# motorcontrol.net
KiCad netlist of a schematic drawn in EAGLE
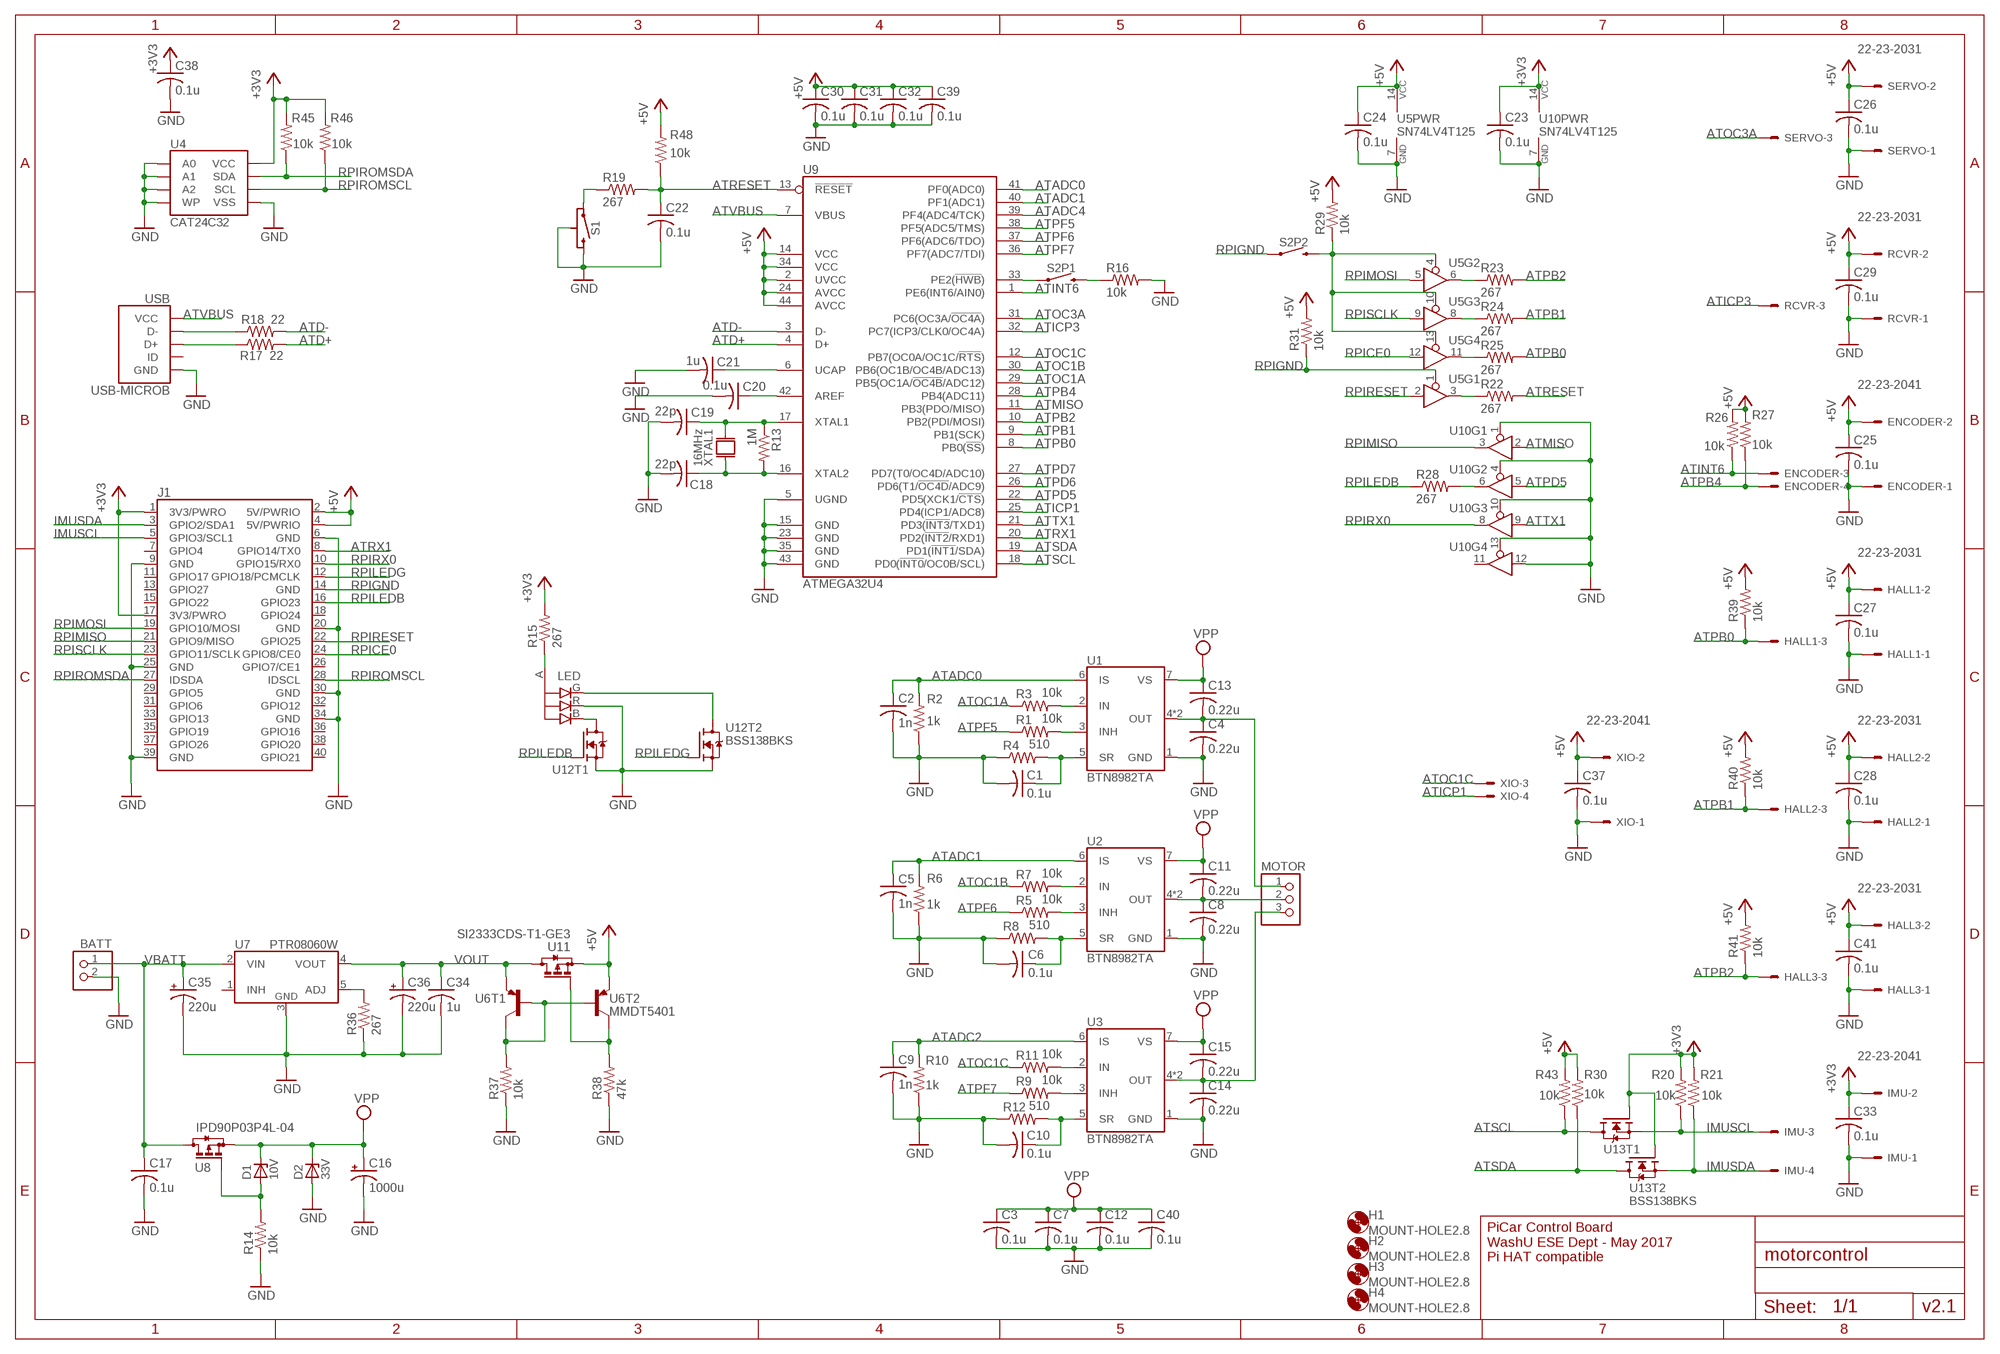
[diagram p0: schematic, sheet 1]

(export (version "E")
  (design (tool "Eeschema 10.0.6"))
  (components
    (comp (ref "BATT")
      (value "ULTRAFIT_2CIRCVCLIP")
      (footprint "eagle-import:ULTRAFIT_2CIRC_VERTCLIP")
      (libsource (lib "eagle-import") (part "ULTRAFIT_2CIRCVCLIP"))
    )
    (comp (ref "C1")
      (value "0.1u")
      (footprint "eagle-import:C1206")
      (libsource (lib "eagle-import") (part "C-USC1206"))
    )
    (comp (ref "C2")
      (value "1n")
      (footprint "eagle-import:C1206")
      (libsource (lib "eagle-import") (part "C-USC1206"))
    )
    (comp (ref "C3")
      (value "0.1u")
      (footprint "eagle-import:C1206")
      (libsource (lib "eagle-import") (part "C-USC1206"))
    )
    (comp (ref "C4")
      (value "0.22u")
      (footprint "eagle-import:C1206")
      (libsource (lib "eagle-import") (part "C-USC1206"))
    )
    (comp (ref "C5")
      (value "1n")
      (footprint "eagle-import:C1206")
      (libsource (lib "eagle-import") (part "C-USC1206"))
    )
    (comp (ref "C6")
      (value "0.1u")
      (footprint "eagle-import:C1206")
      (libsource (lib "eagle-import") (part "C-USC1206"))
    )
    (comp (ref "C7")
      (value "0.1u")
      (footprint "eagle-import:C1206")
      (libsource (lib "eagle-import") (part "C-USC1206"))
    )
    (comp (ref "C8")
      (value "0.22u")
      (footprint "eagle-import:C1206")
      (libsource (lib "eagle-import") (part "C-USC1206"))
    )
    (comp (ref "C9")
      (value "1n")
      (footprint "eagle-import:C1206")
      (libsource (lib "eagle-import") (part "C-USC1206"))
    )
    (comp (ref "C10")
      (value "0.1u")
      (footprint "eagle-import:C1206")
      (libsource (lib "eagle-import") (part "C-USC1206"))
    )
    (comp (ref "C11")
      (value "0.22u")
      (footprint "eagle-import:C1206")
      (libsource (lib "eagle-import") (part "C-USC1206"))
    )
    (comp (ref "C12")
      (value "0.1u")
      (footprint "eagle-import:C1206")
      (libsource (lib "eagle-import") (part "C-USC1206"))
    )
    (comp (ref "C13")
      (value "0.22u")
      (footprint "eagle-import:C1206")
      (libsource (lib "eagle-import") (part "C-USC1206"))
    )
    (comp (ref "C14")
      (value "0.22u")
      (footprint "eagle-import:C1206")
      (libsource (lib "eagle-import") (part "C-USC1206"))
    )
    (comp (ref "C15")
      (value "0.22u")
      (footprint "eagle-import:C1206")
      (libsource (lib "eagle-import") (part "C-USC1206"))
    )
    (comp (ref "C16")
      (value "1000u")
      (footprint "eagle-import:E5-10,5")
      (libsource (lib "eagle-import") (part "CPOL-USE5-10.5"))
    )
    (comp (ref "C17")
      (value "0.1u")
      (footprint "eagle-import:C1206")
      (libsource (lib "eagle-import") (part "C-USC1206"))
    )
    (comp (ref "C18")
      (value "22p")
      (footprint "eagle-import:C1206")
      (libsource (lib "eagle-import") (part "C-USC1206"))
    )
    (comp (ref "C19")
      (value "22p")
      (footprint "eagle-import:C1206")
      (libsource (lib "eagle-import") (part "C-USC1206"))
    )
    (comp (ref "C20")
      (value "0.1u")
      (footprint "eagle-import:C1206")
      (libsource (lib "eagle-import") (part "C-USC1206"))
    )
    (comp (ref "C21")
      (value "1u")
      (footprint "eagle-import:C1206")
      (libsource (lib "eagle-import") (part "C-USC1206"))
    )
    (comp (ref "C22")
      (value "0.1u")
      (footprint "eagle-import:C1206")
      (libsource (lib "eagle-import") (part "C-USC1206"))
    )
    (comp (ref "C23")
      (value "0.1u")
      (footprint "eagle-import:C1206")
      (libsource (lib "eagle-import") (part "C-USC1206"))
    )
    (comp (ref "C24")
      (value "0.1u")
      (footprint "eagle-import:C1206")
      (libsource (lib "eagle-import") (part "C-USC1206"))
    )
    (comp (ref "C25")
      (value "0.1u")
      (footprint "eagle-import:C1206")
      (libsource (lib "eagle-import") (part "C-USC1206"))
    )
    (comp (ref "C26")
      (value "0.1u")
      (footprint "eagle-import:C1206")
      (libsource (lib "eagle-import") (part "C-USC1206"))
    )
    (comp (ref "C27")
      (value "0.1u")
      (footprint "eagle-import:C1206")
      (libsource (lib "eagle-import") (part "C-USC1206"))
    )
    (comp (ref "C28")
      (value "0.1u")
      (footprint "eagle-import:C1206")
      (libsource (lib "eagle-import") (part "C-USC1206"))
    )
    (comp (ref "C29")
      (value "0.1u")
      (footprint "eagle-import:C1206")
      (libsource (lib "eagle-import") (part "C-USC1206"))
    )
    (comp (ref "C30")
      (value "0.1u")
      (footprint "eagle-import:C1206")
      (libsource (lib "eagle-import") (part "C-USC1206"))
    )
    (comp (ref "C31")
      (value "0.1u")
      (footprint "eagle-import:C1206")
      (libsource (lib "eagle-import") (part "C-USC1206"))
    )
    (comp (ref "C32")
      (value "0.1u")
      (footprint "eagle-import:C1206")
      (libsource (lib "eagle-import") (part "C-USC1206"))
    )
    (comp (ref "C33")
      (value "0.1u")
      (footprint "eagle-import:C1206")
      (libsource (lib "eagle-import") (part "C-USC1206"))
    )
    (comp (ref "C34")
      (value "1u")
      (footprint "eagle-import:C1206")
      (libsource (lib "eagle-import") (part "C-USC1206"))
    )
    (comp (ref "C35")
      (value "220u")
      (footprint "eagle-import:E3,5-8")
      (libsource (lib "eagle-import") (part "CPOL-USE3.5-8"))
    )
    (comp (ref "C36")
      (value "220u")
      (footprint "eagle-import:E3,5-8")
      (libsource (lib "eagle-import") (part "CPOL-USE3.5-8"))
    )
    (comp (ref "C37")
      (value "0.1u")
      (footprint "eagle-import:C1206")
      (libsource (lib "eagle-import") (part "C-USC1206"))
    )
    (comp (ref "C38")
      (value "0.1u")
      (footprint "eagle-import:C1206")
      (libsource (lib "eagle-import") (part "C-USC1206"))
    )
    (comp (ref "C39")
      (value "0.1u")
      (footprint "eagle-import:C1206")
      (libsource (lib "eagle-import") (part "C-USC1206"))
    )
    (comp (ref "C40")
      (value "0.1u")
      (footprint "eagle-import:C1206")
      (libsource (lib "eagle-import") (part "C-USC1206"))
    )
    (comp (ref "C41")
      (value "0.1u")
      (footprint "eagle-import:C1206")
      (libsource (lib "eagle-import") (part "C-USC1206"))
    )
    (comp (ref "D1")
      (value "10V")
      (footprint "eagle-import:SOD123")
      (libsource (lib "eagle-import") (part "ZENER_DIODESOD123"))
    )
    (comp (ref "D2")
      (value "33V")
      (footprint "eagle-import:SMA")
      (libsource (lib "eagle-import") (part "ZENER_DIODESMA"))
    )
    (comp (ref "ENCODER")
      (value "22-23-2041")
      (footprint "eagle-import:22-23-2041")
      (fields (field (name "MF") "MOLEX"))
      (libsource (lib "eagle-import") (part "22-23-2041"))
    )
    (comp (ref "H1")
      (value "MOUNT-HOLE2.8")
      (footprint "eagle-import:2,8")
      (libsource (lib "eagle-import") (part "MOUNT-HOLE2.8"))
    )
    (comp (ref "H2")
      (value "MOUNT-HOLE2.8")
      (footprint "eagle-import:2,8")
      (libsource (lib "eagle-import") (part "MOUNT-HOLE2.8"))
    )
    (comp (ref "H3")
      (value "MOUNT-HOLE2.8")
      (footprint "eagle-import:2,8")
      (libsource (lib "eagle-import") (part "MOUNT-HOLE2.8"))
    )
    (comp (ref "H4")
      (value "MOUNT-HOLE2.8")
      (footprint "eagle-import:2,8")
      (libsource (lib "eagle-import") (part "MOUNT-HOLE2.8"))
    )
    (comp (ref "HALL1")
      (value "22-23-2031")
      (footprint "eagle-import:22-23-2031")
      (fields (field (name "MF") "MOLEX"))
      (libsource (lib "eagle-import") (part "22-23-2031"))
    )
    (comp (ref "HALL2")
      (value "22-23-2031")
      (footprint "eagle-import:22-23-2031")
      (fields (field (name "MF") "MOLEX"))
      (libsource (lib "eagle-import") (part "22-23-2031"))
    )
    (comp (ref "HALL3")
      (value "22-23-2031")
      (footprint "eagle-import:22-23-2031")
      (fields (field (name "MF") "MOLEX"))
      (libsource (lib "eagle-import") (part "22-23-2031"))
    )
    (comp (ref "IMU")
      (value "22-23-2041")
      (footprint "eagle-import:22-23-2041")
      (fields (field (name "MF") "MOLEX"))
      (libsource (lib "eagle-import") (part "22-23-2041"))
    )
    (comp (ref "J1")
      (value "RPIHEADER_2.54-SMD")
      (footprint "eagle-import:RPI_SMD")
      (libsource (lib "eagle-import") (part "RPIHEADER_2.54-SMD"))
    )
    (comp (ref "LED")
      (value "LED_3COLOR_COMMONA1411")
      (footprint "eagle-import:150141M173100")
      (libsource (lib "eagle-import") (part "LED_3COLOR_COMMONA1411"))
    )
    (comp (ref "MOTOR")
      (value "ULTRAFIT_3CIRCVCLIP")
      (footprint "eagle-import:ULTRAFIT_3CIRC_VERTCLIP")
      (libsource (lib "eagle-import") (part "ULTRAFIT_3CIRCVCLIP"))
    )
    (comp (ref "R1")
      (value "10k")
      (footprint "eagle-import:R1206")
      (libsource (lib "eagle-import") (part "R-US_R1206"))
    )
    (comp (ref "R2")
      (value "1k")
      (footprint "eagle-import:R1206")
      (libsource (lib "eagle-import") (part "R-US_R1206"))
    )
    (comp (ref "R3")
      (value "10k")
      (footprint "eagle-import:R1206")
      (libsource (lib "eagle-import") (part "R-US_R1206"))
    )
    (comp (ref "R4")
      (value "510")
      (footprint "eagle-import:R1206")
      (libsource (lib "eagle-import") (part "R-US_R1206"))
    )
    (comp (ref "R5")
      (value "10k")
      (footprint "eagle-import:R1206")
      (libsource (lib "eagle-import") (part "R-US_R1206"))
    )
    (comp (ref "R6")
      (value "1k")
      (footprint "eagle-import:R1206")
      (libsource (lib "eagle-import") (part "R-US_R1206"))
    )
    (comp (ref "R7")
      (value "10k")
      (footprint "eagle-import:R1206")
      (libsource (lib "eagle-import") (part "R-US_R1206"))
    )
    (comp (ref "R8")
      (value "510")
      (footprint "eagle-import:R1206")
      (libsource (lib "eagle-import") (part "R-US_R1206"))
    )
    (comp (ref "R9")
      (value "10k")
      (footprint "eagle-import:R1206")
      (libsource (lib "eagle-import") (part "R-US_R1206"))
    )
    (comp (ref "R10")
      (value "1k")
      (footprint "eagle-import:R1206")
      (libsource (lib "eagle-import") (part "R-US_R1206"))
    )
    (comp (ref "R11")
      (value "10k")
      (footprint "eagle-import:R1206")
      (libsource (lib "eagle-import") (part "R-US_R1206"))
    )
    (comp (ref "R12")
      (value "510")
      (footprint "eagle-import:R1206")
      (libsource (lib "eagle-import") (part "R-US_R1206"))
    )
    (comp (ref "R13")
      (value "1M")
      (footprint "eagle-import:R1206")
      (libsource (lib "eagle-import") (part "R-US_R1206"))
    )
    (comp (ref "R14")
      (value "10k")
      (footprint "eagle-import:R1206")
      (libsource (lib "eagle-import") (part "R-US_R1206"))
    )
    (comp (ref "R15")
      (value "267")
      (footprint "eagle-import:R1206")
      (libsource (lib "eagle-import") (part "R-US_R1206"))
    )
    (comp (ref "R16")
      (value "10k")
      (footprint "eagle-import:R1206")
      (libsource (lib "eagle-import") (part "R-US_R1206"))
    )
    (comp (ref "R17")
      (value "22")
      (footprint "eagle-import:R1206")
      (libsource (lib "eagle-import") (part "R-US_R1206"))
    )
    (comp (ref "R18")
      (value "22")
      (footprint "eagle-import:R1206")
      (libsource (lib "eagle-import") (part "R-US_R1206"))
    )
    (comp (ref "R19")
      (value "267")
      (footprint "eagle-import:R1206")
      (libsource (lib "eagle-import") (part "R-US_R1206"))
    )
    (comp (ref "R20")
      (value "10k")
      (footprint "eagle-import:R1206")
      (libsource (lib "eagle-import") (part "R-US_R1206"))
    )
    (comp (ref "R21")
      (value "10k")
      (footprint "eagle-import:R1206")
      (libsource (lib "eagle-import") (part "R-US_R1206"))
    )
    (comp (ref "R22")
      (value "267")
      (footprint "eagle-import:R1206")
      (libsource (lib "eagle-import") (part "R-US_R1206"))
    )
    (comp (ref "R23")
      (value "267")
      (footprint "eagle-import:R1206")
      (libsource (lib "eagle-import") (part "R-US_R1206"))
    )
    (comp (ref "R24")
      (value "267")
      (footprint "eagle-import:R1206")
      (libsource (lib "eagle-import") (part "R-US_R1206"))
    )
    (comp (ref "R25")
      (value "267")
      (footprint "eagle-import:R1206")
      (libsource (lib "eagle-import") (part "R-US_R1206"))
    )
    (comp (ref "R26")
      (value "10k")
      (footprint "eagle-import:R1206")
      (libsource (lib "eagle-import") (part "R-US_R1206"))
    )
    (comp (ref "R27")
      (value "10k")
      (footprint "eagle-import:R1206")
      (libsource (lib "eagle-import") (part "R-US_R1206"))
    )
    (comp (ref "R28")
      (value "267")
      (footprint "eagle-import:R1206")
      (libsource (lib "eagle-import") (part "R-US_R1206"))
    )
    (comp (ref "R29")
      (value "10k")
      (footprint "eagle-import:R1206")
      (libsource (lib "eagle-import") (part "R-US_R1206"))
    )
    (comp (ref "R30")
      (value "10k")
      (footprint "eagle-import:R1206")
      (libsource (lib "eagle-import") (part "R-US_R1206"))
    )
    (comp (ref "R31")
      (value "10k")
      (footprint "eagle-import:R1206")
      (libsource (lib "eagle-import") (part "R-US_R1206"))
    )
    (comp (ref "R36")
      (value "267")
      (footprint "eagle-import:R1206")
      (libsource (lib "eagle-import") (part "R-US_R1206"))
    )
    (comp (ref "R37")
      (value "10k")
      (footprint "eagle-import:R1206")
      (libsource (lib "eagle-import") (part "R-US_R1206"))
    )
    (comp (ref "R38")
      (value "47k")
      (footprint "eagle-import:R1206")
      (libsource (lib "eagle-import") (part "R-US_R1206"))
    )
    (comp (ref "R39")
      (value "10k")
      (footprint "eagle-import:R1206")
      (libsource (lib "eagle-import") (part "R-US_R1206"))
    )
    (comp (ref "R40")
      (value "10k")
      (footprint "eagle-import:R1206")
      (libsource (lib "eagle-import") (part "R-US_R1206"))
    )
    (comp (ref "R41")
      (value "10k")
      (footprint "eagle-import:R1206")
      (libsource (lib "eagle-import") (part "R-US_R1206"))
    )
    (comp (ref "R43")
      (value "10k")
      (footprint "eagle-import:R1206")
      (libsource (lib "eagle-import") (part "R-US_R1206"))
    )
    (comp (ref "R45")
      (value "10k")
      (footprint "eagle-import:R1206")
      (libsource (lib "eagle-import") (part "R-US_R1206"))
    )
    (comp (ref "R46")
      (value "10k")
      (footprint "eagle-import:R1206")
      (libsource (lib "eagle-import") (part "R-US_R1206"))
    )
    (comp (ref "R48")
      (value "10k")
      (footprint "eagle-import:R1206")
      (libsource (lib "eagle-import") (part "R-US_R1206"))
    )
    (comp (ref "RCVR")
      (value "22-23-2031")
      (footprint "eagle-import:22-23-2031")
      (fields (field (name "MF") "MOLEX"))
      (libsource (lib "eagle-import") (part "22-23-2031"))
    )
    (comp (ref "S1")
      (value "SWITCH-GND")
      (footprint "eagle-import:B3F-312X")
      (libsource (lib "eagle-import") (part "SWITCH-GND"))
    )
    (comp (ref "S2")
      (value "A6HF-2DIP")
      (footprint "eagle-import:A6HF-2DIP")
      (libsource (lib "eagle-import") (part "A6HF-2DIP"))
    )
    (comp (ref "SERVO")
      (value "22-23-2031")
      (footprint "eagle-import:22-23-2031")
      (fields (field (name "MF") "MOLEX"))
      (libsource (lib "eagle-import") (part "22-23-2031"))
    )
    (comp (ref "U1")
      (value "BTN8982TA")
      (footprint "eagle-import:TO263-7")
      (libsource (lib "eagle-import") (part "BTN8982TA"))
    )
    (comp (ref "U2")
      (value "BTN8982TA")
      (footprint "eagle-import:TO263-7")
      (libsource (lib "eagle-import") (part "BTN8982TA"))
    )
    (comp (ref "U3")
      (value "BTN8982TA")
      (footprint "eagle-import:TO263-7")
      (libsource (lib "eagle-import") (part "BTN8982TA"))
    )
    (comp (ref "U4")
      (value "CAT24C32")
      (footprint "eagle-import:SOIC8")
      (libsource (lib "eagle-import") (part "CAT24C32"))
    )
    (comp (ref "U5")
      (value "SN74LV4T125")
      (footprint "eagle-import:TSSOP14")
      (libsource (lib "eagle-import") (part "SN74LV4T125"))
    )
    (comp (ref "U6")
      (value "MMDT5401")
      (footprint "eagle-import:SOT363")
      (libsource (lib "eagle-import") (part "MMDT5401"))
    )
    (comp (ref "U7")
      (value "PTR08060W")
      (footprint "eagle-import:EDP_MODULE")
      (libsource (lib "eagle-import") (part "PTR08060W"))
    )
    (comp (ref "U8")
      (value "IPD90P03P4L-04")
      (footprint "eagle-import:TO252-3-11")
      (libsource (lib "eagle-import") (part "IPD90P03P4L-04"))
    )
    (comp (ref "U9")
      (value "ATMEGA32U4")
      (footprint "eagle-import:TQFP44")
      (libsource (lib "eagle-import") (part "ATMEGA32U4"))
    )
    (comp (ref "U10")
      (value "SN74LV4T125")
      (footprint "eagle-import:TSSOP14")
      (libsource (lib "eagle-import") (part "SN74LV4T125"))
    )
    (comp (ref "U11")
      (value "SI2333CDS-T1-GE3")
      (footprint "eagle-import:SOT23-3")
      (libsource (lib "eagle-import") (part "SI2333CDS-T1-GE3"))
    )
    (comp (ref "U12")
      (value "BSS138BKS")
      (footprint "eagle-import:SOT363")
      (libsource (lib "eagle-import") (part "BSS138BKS"))
    )
    (comp (ref "U13")
      (value "BSS138BKS")
      (footprint "eagle-import:SOT363")
      (libsource (lib "eagle-import") (part "BSS138BKS"))
    )
    (comp (ref "USB")
      (value "USB-MICROB")
      (footprint "eagle-import:FCI-10103594-0001LF")
      (libsource (lib "eagle-import") (part "USB-MICROB"))
    )
    (comp (ref "XIO")
      (value "22-23-2041")
      (footprint "eagle-import:22-23-2041")
      (fields (field (name "MF") "MOLEX"))
      (libsource (lib "eagle-import") (part "22-23-2041"))
    )
    (comp (ref "XTAL1")
      (value "16MHz")
      (footprint "eagle-import:ABLS7M2")
      (libsource (lib "eagle-import") (part "XTALABLS7M2"))
    )
  )
  (nets
    (net (code "1") (name "+3V3") (class "Default")
      (node (ref "C23") (pin "1") (pinfunction "1_1") (pintype "passive"))
      (node (ref "C33") (pin "1") (pinfunction "1_1") (pintype "passive"))
      (node (ref "C38") (pin "1") (pinfunction "1_1") (pintype "passive"))
      (node (ref "IMU") (pin "2") (pinfunction "S_2") (pintype "passive"))
      (node (ref "J1") (pin "1") (pinfunction "3V3/PWRO_1") (pintype "passive"))
      (node (ref "J1") (pin "17") (pinfunction "3V3/PWRO_17") (pintype "passive"))
      (node (ref "R15") (pin "2") (pinfunction "2_2") (pintype "passive"))
      (node (ref "R20") (pin "2") (pinfunction "2_2") (pintype "passive"))
      (node (ref "R21") (pin "2") (pinfunction "2_2") (pintype "passive"))
      (node (ref "R45") (pin "2") (pinfunction "2_2") (pintype "passive"))
      (node (ref "R46") (pin "2") (pinfunction "2_2") (pintype "passive"))
      (node (ref "U10") (pin "14") (pinfunction "VCC_14") (pintype "power_in"))
      (node (ref "U13") (pin "2") (pinfunction "G_2") (pintype "passive"))
      (node (ref "U13") (pin "5") (pinfunction "G_5") (pintype "passive"))
      (node (ref "U4") (pin "8") (pinfunction "VCC_8") (pintype "power_in"))
    )
    (net (code "2") (name "+5V") (class "Default")
      (node (ref "C24") (pin "1") (pinfunction "1_1") (pintype "passive"))
      (node (ref "C25") (pin "1") (pinfunction "1_1") (pintype "passive"))
      (node (ref "C26") (pin "1") (pinfunction "1_1") (pintype "passive"))
      (node (ref "C27") (pin "1") (pinfunction "1_1") (pintype "passive"))
      (node (ref "C28") (pin "1") (pinfunction "1_1") (pintype "passive"))
      (node (ref "C29") (pin "1") (pinfunction "1_1") (pintype "passive"))
      (node (ref "C30") (pin "1") (pinfunction "1_1") (pintype "passive"))
      (node (ref "C31") (pin "1") (pinfunction "1_1") (pintype "passive"))
      (node (ref "C32") (pin "1") (pinfunction "1_1") (pintype "passive"))
      (node (ref "C37") (pin "1") (pinfunction "1_1") (pintype "passive"))
      (node (ref "C39") (pin "1") (pinfunction "1_1") (pintype "passive"))
      (node (ref "C41") (pin "1") (pinfunction "1_1") (pintype "passive"))
      (node (ref "ENCODER") (pin "2") (pinfunction "S_2") (pintype "passive"))
      (node (ref "HALL1") (pin "2") (pinfunction "S_2") (pintype "passive"))
      (node (ref "HALL2") (pin "2") (pinfunction "S_2") (pintype "passive"))
      (node (ref "HALL3") (pin "2") (pinfunction "S_2") (pintype "passive"))
      (node (ref "J1") (pin "2") (pinfunction "5V/PWRIO_2") (pintype "passive"))
      (node (ref "J1") (pin "4") (pinfunction "5V/PWRIO_4") (pintype "passive"))
      (node (ref "R26") (pin "2") (pinfunction "2_2") (pintype "passive"))
      (node (ref "R27") (pin "2") (pinfunction "2_2") (pintype "passive"))
      (node (ref "R29") (pin "2") (pinfunction "2_2") (pintype "passive"))
      (node (ref "R30") (pin "2") (pinfunction "2_2") (pintype "passive"))
      (node (ref "R31") (pin "2") (pinfunction "2_2") (pintype "passive"))
      (node (ref "R39") (pin "2") (pinfunction "2_2") (pintype "passive"))
      (node (ref "R40") (pin "2") (pinfunction "2_2") (pintype "passive"))
      (node (ref "R41") (pin "2") (pinfunction "2_2") (pintype "passive"))
      (node (ref "R43") (pin "2") (pinfunction "2_2") (pintype "passive"))
      (node (ref "R48") (pin "2") (pinfunction "2_2") (pintype "passive"))
      (node (ref "RCVR") (pin "2") (pinfunction "S_2") (pintype "passive"))
      (node (ref "SERVO") (pin "2") (pinfunction "S_2") (pintype "passive"))
      (node (ref "U11") (pin "2") (pinfunction "S_2") (pintype "passive"))
      (node (ref "U5") (pin "14") (pinfunction "VCC_14") (pintype "power_in"))
      (node (ref "U6") (pin "4") (pinfunction "E_4") (pintype "passive"))
      (node (ref "U9") (pin "14") (pinfunction "VCC_14") (pintype "bidirectional"))
      (node (ref "U9") (pin "2") (pinfunction "UVCC_2") (pintype "bidirectional"))
      (node (ref "U9") (pin "24") (pinfunction "AVCC_24") (pintype "bidirectional"))
      (node (ref "U9") (pin "34") (pinfunction "VCC_34") (pintype "bidirectional"))
      (node (ref "U9") (pin "44") (pinfunction "AVCC_44") (pintype "bidirectional"))
      (node (ref "XIO") (pin "2") (pinfunction "S_2") (pintype "passive"))
    )
    (net (code "3") (name "/ATADC0") (class "Default")
      (node (ref "C2") (pin "1") (pinfunction "1_1") (pintype "passive"))
      (node (ref "R2") (pin "2") (pinfunction "2_2") (pintype "passive"))
      (node (ref "U1") (pin "6") (pinfunction "IS_6") (pintype "output"))
      (node (ref "U9") (pin "41") (pinfunction "PF0(ADC0)_41") (pintype "bidirectional"))
    )
    (net (code "4") (name "/ATADC1") (class "Default")
      (node (ref "C5") (pin "1") (pinfunction "1_1") (pintype "passive"))
      (node (ref "R6") (pin "2") (pinfunction "2_2") (pintype "passive"))
      (node (ref "U2") (pin "6") (pinfunction "IS_6") (pintype "output"))
      (node (ref "U9") (pin "40") (pinfunction "PF1(ADC1)_40") (pintype "bidirectional"))
    )
    (net (code "5") (name "/ATADC2") (class "Default")
      (node (ref "C9") (pin "1") (pinfunction "1_1") (pintype "passive"))
      (node (ref "R10") (pin "2") (pinfunction "2_2") (pintype "passive"))
      (node (ref "U3") (pin "6") (pinfunction "IS_6") (pintype "output"))
    )
    (net (code "6") (name "/ATADC4") (class "Default")
      (node (ref "U9") (pin "39") (pinfunction "PF4(ADC4/TCK)_39") (pintype "bidirectional"))
    )
    (net (code "7") (name "/ATD+") (class "Default")
      (node (ref "R17") (pin "2") (pinfunction "2_2") (pintype "passive"))
      (node (ref "U9") (pin "4") (pinfunction "D+_4") (pintype "bidirectional"))
    )
    (net (code "8") (name "/ATD-") (class "Default")
      (node (ref "R18") (pin "2") (pinfunction "2_2") (pintype "passive"))
      (node (ref "U9") (pin "3") (pinfunction "D-_3") (pintype "bidirectional"))
    )
    (net (code "9") (name "/ATICP1") (class "Default")
      (node (ref "U9") (pin "25") (pinfunction "PD4(ICP1/ADC8)_25") (pintype "bidirectional"))
      (node (ref "XIO") (pin "4") (pinfunction "S_4") (pintype "passive"))
    )
    (net (code "10") (name "/ATICP3") (class "Default")
      (node (ref "RCVR") (pin "3") (pinfunction "S_3") (pintype "passive"))
      (node (ref "U9") (pin "32") (pinfunction "PC7(ICP3/CLK0/OC4A)_32") (pintype "bidirectional"))
    )
    (net (code "11") (name "/ATINT6") (class "Default")
      (node (ref "ENCODER") (pin "3") (pinfunction "S_3") (pintype "passive"))
      (node (ref "R26") (pin "1") (pinfunction "1_1") (pintype "passive"))
      (node (ref "U9") (pin "1") (pinfunction "PE6(INT6/AIN0)_1") (pintype "bidirectional"))
    )
    (net (code "12") (name "/ATMISO") (class "Default")
      (node (ref "U10") (pin "2") (pinfunction "I_2") (pintype "input"))
      (node (ref "U9") (pin "11") (pinfunction "PB3(PDO/MISO)_11") (pintype "bidirectional"))
    )
    (net (code "13") (name "/ATOC1A") (class "Default")
      (node (ref "R3") (pin "1") (pinfunction "1_1") (pintype "passive"))
      (node (ref "U9") (pin "29") (pinfunction "PB5(OC1A/~{OC4B}/ADC12)_29") (pintype "bidirectional"))
    )
    (net (code "14") (name "/ATOC1B") (class "Default")
      (node (ref "R7") (pin "1") (pinfunction "1_1") (pintype "passive"))
      (node (ref "U9") (pin "30") (pinfunction "PB6(OC1B/OC4B/ADC13)_30") (pintype "bidirectional"))
    )
    (net (code "15") (name "/ATOC1C") (class "Default")
      (node (ref "R11") (pin "1") (pinfunction "1_1") (pintype "passive"))
      (node (ref "U9") (pin "12") (pinfunction "PB7(OC0A/OC1C/~{RTS})_12") (pintype "bidirectional"))
      (node (ref "XIO") (pin "3") (pinfunction "S_3") (pintype "passive"))
    )
    (net (code "16") (name "/ATOC3A") (class "Default")
      (node (ref "SERVO") (pin "3") (pinfunction "S_3") (pintype "passive"))
      (node (ref "U9") (pin "31") (pinfunction "PC6(OC3A/~{OC4A})_31") (pintype "bidirectional"))
    )
    (net (code "17") (name "/ATPB0") (class "Default")
      (node (ref "HALL1") (pin "3") (pinfunction "S_3") (pintype "passive"))
      (node (ref "R25") (pin "2") (pinfunction "2_2") (pintype "passive"))
      (node (ref "R39") (pin "1") (pinfunction "1_1") (pintype "passive"))
      (node (ref "U9") (pin "8") (pinfunction "PB0(~{SS})_8") (pintype "bidirectional"))
    )
    (net (code "18") (name "/ATPB1") (class "Default")
      (node (ref "HALL2") (pin "3") (pinfunction "S_3") (pintype "passive"))
      (node (ref "R24") (pin "2") (pinfunction "2_2") (pintype "passive"))
      (node (ref "R40") (pin "1") (pinfunction "1_1") (pintype "passive"))
      (node (ref "U9") (pin "9") (pinfunction "PB1(SCK)_9") (pintype "bidirectional"))
    )
    (net (code "19") (name "/ATPB2") (class "Default")
      (node (ref "HALL3") (pin "3") (pinfunction "S_3") (pintype "passive"))
      (node (ref "R23") (pin "2") (pinfunction "2_2") (pintype "passive"))
      (node (ref "R41") (pin "1") (pinfunction "1_1") (pintype "passive"))
      (node (ref "U9") (pin "10") (pinfunction "PB2(PDI/MOSI)_10") (pintype "bidirectional"))
    )
    (net (code "20") (name "/ATPB4") (class "Default")
      (node (ref "ENCODER") (pin "4") (pinfunction "S_4") (pintype "passive"))
      (node (ref "R27") (pin "1") (pinfunction "1_1") (pintype "passive"))
      (node (ref "U9") (pin "28") (pinfunction "PB4(ADC11)_28") (pintype "bidirectional"))
    )
    (net (code "21") (name "/ATPD5") (class "Default")
      (node (ref "U10") (pin "5") (pinfunction "I_5") (pintype "input"))
      (node (ref "U9") (pin "22") (pinfunction "PD5(XCK1/~{CTS})_22") (pintype "bidirectional"))
    )
    (net (code "22") (name "/ATPD6") (class "Default")
      (node (ref "U9") (pin "26") (pinfunction "PD6(T1/~{OC4D}/ADC9)_26") (pintype "bidirectional"))
    )
    (net (code "23") (name "/ATPD7") (class "Default")
      (node (ref "U9") (pin "27") (pinfunction "PD7(T0/OC4D/ADC10)_27") (pintype "bidirectional"))
    )
    (net (code "24") (name "/ATPF5") (class "Default")
      (node (ref "R1") (pin "1") (pinfunction "1_1") (pintype "passive"))
      (node (ref "U9") (pin "38") (pinfunction "PF5(ADC5/TMS)_38") (pintype "bidirectional"))
    )
    (net (code "25") (name "/ATPF6") (class "Default")
      (node (ref "R5") (pin "1") (pinfunction "1_1") (pintype "passive"))
      (node (ref "U9") (pin "37") (pinfunction "PF6(ADC6/TDO)_37") (pintype "bidirectional"))
    )
    (net (code "26") (name "/ATPF7") (class "Default")
      (node (ref "R9") (pin "1") (pinfunction "1_1") (pintype "passive"))
      (node (ref "U9") (pin "36") (pinfunction "PF7(ADC7/TDI)_36") (pintype "bidirectional"))
    )
    (net (code "27") (name "/ATRESET") (class "Default")
      (node (ref "C22") (pin "1") (pinfunction "1_1") (pintype "passive"))
      (node (ref "R19") (pin "2") (pinfunction "2_2") (pintype "passive"))
      (node (ref "R22") (pin "2") (pinfunction "2_2") (pintype "passive"))
      (node (ref "R48") (pin "1") (pinfunction "1_1") (pintype "passive"))
      (node (ref "U9") (pin "13") (pinfunction "~{RESET}_13") (pintype "bidirectional"))
    )
    (net (code "28") (name "/ATRX1") (class "Default")
      (node (ref "J1") (pin "8") (pinfunction "GPIO14/TX0_8") (pintype "passive"))
      (node (ref "U9") (pin "20") (pinfunction "PD2(~{INT2}/RXD1)_20") (pintype "bidirectional"))
    )
    (net (code "29") (name "/ATSCL") (class "Default")
      (node (ref "R43") (pin "1") (pinfunction "1_1") (pintype "passive"))
      (node (ref "U13") (pin "6") (pinfunction "D_6") (pintype "passive"))
      (node (ref "U9") (pin "18") (pinfunction "PD0(~{INT0}/OC0B/SCL)_18") (pintype "bidirectional"))
    )
    (net (code "30") (name "/ATSDA") (class "Default")
      (node (ref "R30") (pin "1") (pinfunction "1_1") (pintype "passive"))
      (node (ref "U13") (pin "3") (pinfunction "D_3") (pintype "passive"))
      (node (ref "U9") (pin "19") (pinfunction "PD1(~{INT1}/SDA)_19") (pintype "bidirectional"))
    )
    (net (code "31") (name "/ATTX1") (class "Default")
      (node (ref "U10") (pin "9") (pinfunction "I_9") (pintype "input"))
      (node (ref "U9") (pin "21") (pinfunction "PD3(~{INT3}/TXD1)_21") (pintype "bidirectional"))
    )
    (net (code "32") (name "/ATVBUS") (class "Default")
      (node (ref "U9") (pin "7") (pinfunction "VBUS_7") (pintype "bidirectional"))
      (node (ref "USB") (pin "1") (pinfunction "VCC_1") (pintype "passive"))
    )
    (net (code "33") (name "/IMUSCL") (class "Default")
      (node (ref "IMU") (pin "3") (pinfunction "S_3") (pintype "passive"))
      (node (ref "J1") (pin "5") (pinfunction "GPIO3/SCL1_5") (pintype "passive"))
      (node (ref "R20") (pin "1") (pinfunction "1_1") (pintype "passive"))
      (node (ref "U13") (pin "1") (pinfunction "S_1") (pintype "passive"))
    )
    (net (code "34") (name "/IMUSDA") (class "Default")
      (node (ref "IMU") (pin "4") (pinfunction "S_4") (pintype "passive"))
      (node (ref "J1") (pin "3") (pinfunction "GPIO2/SDA1_3") (pintype "passive"))
      (node (ref "R21") (pin "1") (pinfunction "1_1") (pintype "passive"))
      (node (ref "U13") (pin "4") (pinfunction "S_4") (pintype "passive"))
    )
    (net (code "35") (name "/RPICE0") (class "Default")
      (node (ref "J1") (pin "24") (pinfunction "GPIO8/CE0_24") (pintype "passive"))
      (node (ref "U5") (pin "12") (pinfunction "I_12") (pintype "input"))
    )
    (net (code "36") (name "/RPIGND") (class "Default")
      (node (ref "J1") (pin "14") (pinfunction "GND_14") (pintype "passive"))
      (node (ref "R31") (pin "1") (pinfunction "1_1") (pintype "passive"))
      (node (ref "S2") (pin "P2.1") (pinfunction "1_P2.1") (pintype "passive"))
      (node (ref "U5") (pin "1") (pinfunction "OE_1") (pintype "input"))
    )
    (net (code "37") (name "/RPILEDB") (class "Default")
      (node (ref "J1") (pin "16") (pinfunction "GPIO23_16") (pintype "passive"))
      (node (ref "R28") (pin "1") (pinfunction "1_1") (pintype "passive"))
      (node (ref "U12") (pin "2") (pinfunction "G_2") (pintype "passive"))
    )
    (net (code "38") (name "/RPILEDG") (class "Default")
      (node (ref "J1") (pin "12") (pinfunction "GPIO18/PCMCLK_12") (pintype "passive"))
      (node (ref "U12") (pin "5") (pinfunction "G_5") (pintype "passive"))
    )
    (net (code "39") (name "/RPIMISO") (class "Default")
      (node (ref "J1") (pin "21") (pinfunction "GPIO9/MISO_21") (pintype "passive"))
      (node (ref "U10") (pin "3") (pinfunction "O_3") (pintype "tri_state"))
    )
    (net (code "40") (name "/RPIMOSI") (class "Default")
      (node (ref "J1") (pin "19") (pinfunction "GPIO10/MOSI_19") (pintype "passive"))
      (node (ref "U5") (pin "5") (pinfunction "I_5") (pintype "input"))
    )
    (net (code "41") (name "/RPIRESET") (class "Default")
      (node (ref "J1") (pin "22") (pinfunction "GPIO25_22") (pintype "passive"))
      (node (ref "U5") (pin "2") (pinfunction "I_2") (pintype "input"))
    )
    (net (code "42") (name "/RPIROMSCL") (class "Default")
      (node (ref "J1") (pin "28") (pinfunction "IDSCL_28") (pintype "passive"))
      (node (ref "R46") (pin "1") (pinfunction "1_1") (pintype "passive"))
      (node (ref "U4") (pin "6") (pinfunction "SCL_6") (pintype "input"))
    )
    (net (code "43") (name "/RPIROMSDA") (class "Default")
      (node (ref "J1") (pin "27") (pinfunction "IDSDA_27") (pintype "passive"))
      (node (ref "R45") (pin "1") (pinfunction "1_1") (pintype "passive"))
      (node (ref "U4") (pin "5") (pinfunction "SDA_5") (pintype "bidirectional"))
    )
    (net (code "44") (name "/RPIRX0") (class "Default")
      (node (ref "J1") (pin "10") (pinfunction "GPIO15/RX0_10") (pintype "passive"))
      (node (ref "U10") (pin "8") (pinfunction "O_8") (pintype "tri_state"))
    )
    (net (code "45") (name "/RPISCLK") (class "Default")
      (node (ref "J1") (pin "23") (pinfunction "GPIO11/SCLK_23") (pintype "passive"))
      (node (ref "U5") (pin "9") (pinfunction "I_9") (pintype "input"))
    )
    (net (code "46") (name "/VBATT") (class "Default")
      (node (ref "BATT") (pin "1") (pinfunction "P1_1") (pintype "passive"))
      (node (ref "C17") (pin "1") (pinfunction "1_1") (pintype "passive"))
      (node (ref "C35") (pin "+") (pinfunction "+_+") (pintype "passive"))
      (node (ref "U7") (pin "2") (pinfunction "VIN_2") (pintype "power_in"))
      (node (ref "U8") (pin "2") (pinfunction "D_2") (pintype "passive"))
    )
    (net (code "47") (name "/VOUT") (class "Default")
      (node (ref "C34") (pin "1") (pinfunction "1_1") (pintype "passive"))
      (node (ref "C36") (pin "+") (pinfunction "+_+") (pintype "passive"))
      (node (ref "U11") (pin "3") (pinfunction "D_3") (pintype "passive"))
      (node (ref "U6") (pin "1") (pinfunction "E_1") (pintype "passive"))
      (node (ref "U7") (pin "4") (pinfunction "VOUT_4") (pintype "power_in"))
    )
    (net (code "48") (name "GND") (class "Default")
      (node (ref "BATT") (pin "2") (pinfunction "P2_2") (pintype "passive"))
      (node (ref "C1") (pin "2") (pinfunction "2_2") (pintype "passive"))
      (node (ref "C10") (pin "2") (pinfunction "2_2") (pintype "passive"))
      (node (ref "C12") (pin "2") (pinfunction "2_2") (pintype "passive"))
      (node (ref "C14") (pin "2") (pinfunction "2_2") (pintype "passive"))
      (node (ref "C16") (pin "-") (pinfunction "-_-") (pintype "passive"))
      (node (ref "C17") (pin "2") (pinfunction "2_2") (pintype "passive"))
      (node (ref "C18") (pin "2") (pinfunction "2_2") (pintype "passive"))
      (node (ref "C19") (pin "2") (pinfunction "2_2") (pintype "passive"))
      (node (ref "C2") (pin "2") (pinfunction "2_2") (pintype "passive"))
      (node (ref "C20") (pin "2") (pinfunction "2_2") (pintype "passive"))
      (node (ref "C21") (pin "2") (pinfunction "2_2") (pintype "passive"))
      (node (ref "C22") (pin "2") (pinfunction "2_2") (pintype "passive"))
      (node (ref "C23") (pin "2") (pinfunction "2_2") (pintype "passive"))
      (node (ref "C24") (pin "2") (pinfunction "2_2") (pintype "passive"))
      (node (ref "C25") (pin "2") (pinfunction "2_2") (pintype "passive"))
      (node (ref "C26") (pin "2") (pinfunction "2_2") (pintype "passive"))
      (node (ref "C27") (pin "2") (pinfunction "2_2") (pintype "passive"))
      (node (ref "C28") (pin "2") (pinfunction "2_2") (pintype "passive"))
      (node (ref "C29") (pin "2") (pinfunction "2_2") (pintype "passive"))
      (node (ref "C3") (pin "2") (pinfunction "2_2") (pintype "passive"))
      (node (ref "C30") (pin "2") (pinfunction "2_2") (pintype "passive"))
      (node (ref "C31") (pin "2") (pinfunction "2_2") (pintype "passive"))
      (node (ref "C32") (pin "2") (pinfunction "2_2") (pintype "passive"))
      (node (ref "C33") (pin "2") (pinfunction "2_2") (pintype "passive"))
      (node (ref "C34") (pin "2") (pinfunction "2_2") (pintype "passive"))
      (node (ref "C35") (pin "-") (pinfunction "-_-") (pintype "passive"))
      (node (ref "C36") (pin "-") (pinfunction "-_-") (pintype "passive"))
      (node (ref "C37") (pin "2") (pinfunction "2_2") (pintype "passive"))
      (node (ref "C38") (pin "2") (pinfunction "2_2") (pintype "passive"))
      (node (ref "C39") (pin "2") (pinfunction "2_2") (pintype "passive"))
      (node (ref "C4") (pin "2") (pinfunction "2_2") (pintype "passive"))
      (node (ref "C40") (pin "2") (pinfunction "2_2") (pintype "passive"))
      (node (ref "C41") (pin "2") (pinfunction "2_2") (pintype "passive"))
      (node (ref "C5") (pin "2") (pinfunction "2_2") (pintype "passive"))
      (node (ref "C6") (pin "2") (pinfunction "2_2") (pintype "passive"))
      (node (ref "C7") (pin "2") (pinfunction "2_2") (pintype "passive"))
      (node (ref "C8") (pin "2") (pinfunction "2_2") (pintype "passive"))
      (node (ref "C9") (pin "2") (pinfunction "2_2") (pintype "passive"))
      (node (ref "D2") (pin "A") (pinfunction "A_A") (pintype "passive"))
      (node (ref "ENCODER") (pin "1") (pinfunction "S_1") (pintype "passive"))
      (node (ref "HALL1") (pin "1") (pinfunction "S_1") (pintype "passive"))
      (node (ref "HALL2") (pin "1") (pinfunction "S_1") (pintype "passive"))
      (node (ref "HALL3") (pin "1") (pinfunction "S_1") (pintype "passive"))
      (node (ref "IMU") (pin "1") (pinfunction "S_1") (pintype "passive"))
      (node (ref "J1") (pin "20") (pinfunction "GND_20") (pintype "passive"))
      (node (ref "J1") (pin "25") (pinfunction "GND_25") (pintype "passive"))
      (node (ref "J1") (pin "30") (pinfunction "GND_30") (pintype "passive"))
      (node (ref "J1") (pin "34") (pinfunction "GND_34") (pintype "passive"))
      (node (ref "J1") (pin "39") (pinfunction "GND_39") (pintype "passive"))
      (node (ref "J1") (pin "6") (pinfunction "GND_6") (pintype "passive"))
      (node (ref "J1") (pin "9") (pinfunction "GND_9") (pintype "passive"))
      (node (ref "LED") (pin "R") (pinfunction "R_R") (pintype "passive"))
      (node (ref "R10") (pin "1") (pinfunction "1_1") (pintype "passive"))
      (node (ref "R12") (pin "1") (pinfunction "1_1") (pintype "passive"))
      (node (ref "R14") (pin "1") (pinfunction "1_1") (pintype "passive"))
      (node (ref "R16") (pin "2") (pinfunction "2_2") (pintype "passive"))
      (node (ref "R2") (pin "1") (pinfunction "1_1") (pintype "passive"))
      (node (ref "R36") (pin "1") (pinfunction "1_1") (pintype "passive"))
      (node (ref "R37") (pin "1") (pinfunction "1_1") (pintype "passive"))
      (node (ref "R38") (pin "1") (pinfunction "1_1") (pintype "passive"))
      (node (ref "R4") (pin "1") (pinfunction "1_1") (pintype "passive"))
      (node (ref "R6") (pin "1") (pinfunction "1_1") (pintype "passive"))
      (node (ref "R8") (pin "1") (pinfunction "1_1") (pintype "passive"))
      (node (ref "RCVR") (pin "1") (pinfunction "S_1") (pintype "passive"))
      (node (ref "S1") (pin "2") (pinfunction "2_2") (pintype "passive"))
      (node (ref "S1") (pin "3") (pinfunction "GND_3") (pintype "passive"))
      (node (ref "S1") (pin "4") (pinfunction "GND_4") (pintype "passive"))
      (node (ref "SERVO") (pin "1") (pinfunction "S_1") (pintype "passive"))
      (node (ref "U1") (pin "1") (pinfunction "GND_1") (pintype "power_in"))
      (node (ref "U10") (pin "1") (pinfunction "OE_1") (pintype "input"))
      (node (ref "U10") (pin "10") (pinfunction "OE_10") (pintype "input"))
      (node (ref "U10") (pin "12") (pinfunction "I_12") (pintype "input"))
      (node (ref "U10") (pin "13") (pinfunction "OE_13") (pintype "input"))
      (node (ref "U10") (pin "4") (pinfunction "OE_4") (pintype "input"))
      (node (ref "U10") (pin "7") (pinfunction "GND_7") (pintype "power_in"))
      (node (ref "U12") (pin "1") (pinfunction "S_1") (pintype "passive"))
      (node (ref "U12") (pin "4") (pinfunction "S_4") (pintype "passive"))
      (node (ref "U2") (pin "1") (pinfunction "GND_1") (pintype "power_in"))
      (node (ref "U3") (pin "1") (pinfunction "GND_1") (pintype "power_in"))
      (node (ref "U4") (pin "1") (pinfunction "A0_1") (pintype "input"))
      (node (ref "U4") (pin "2") (pinfunction "A1_2") (pintype "input"))
      (node (ref "U4") (pin "3") (pinfunction "A2_3") (pintype "input"))
      (node (ref "U4") (pin "4") (pinfunction "VSS_4") (pintype "passive"))
      (node (ref "U4") (pin "7") (pinfunction "WP_7") (pintype "input"))
      (node (ref "U5") (pin "7") (pinfunction "GND_7") (pintype "power_in"))
      (node (ref "U7") (pin "3") (pinfunction "GND_3") (pintype "power_in"))
      (node (ref "U9") (pin "15") (pinfunction "GND_15") (pintype "bidirectional"))
      (node (ref "U9") (pin "23") (pinfunction "GND_23") (pintype "bidirectional"))
      (node (ref "U9") (pin "35") (pinfunction "GND_35") (pintype "bidirectional"))
      (node (ref "U9") (pin "43") (pinfunction "GND_43") (pintype "bidirectional"))
      (node (ref "U9") (pin "5") (pinfunction "UGND_5") (pintype "bidirectional"))
      (node (ref "USB") (pin "5") (pinfunction "GND_5") (pintype "passive"))
      (node (ref "USB") (pin "GND1") (pinfunction "GND_GND1") (pintype "passive"))
      (node (ref "USB") (pin "GND2") (pinfunction "GND_GND2") (pintype "passive"))
      (node (ref "USB") (pin "GND3") (pinfunction "GND_GND3") (pintype "passive"))
      (node (ref "USB") (pin "GND4") (pinfunction "GND_GND4") (pintype "passive"))
      (node (ref "XIO") (pin "1") (pinfunction "S_1") (pintype "passive"))
    )
    (net (code "49") (name "Net-(LED-PadA)") (class "Default")
      (node (ref "LED") (pin "A") (pinfunction "A_A") (pintype "passive"))
      (node (ref "R15") (pin "1") (pinfunction "1_1") (pintype "passive"))
    )
    (net (code "50") (name "Net-(MOTOR-P1)") (class "Default")
      (node (ref "C13") (pin "2") (pinfunction "2_2") (pintype "passive"))
      (node (ref "C4") (pin "1") (pinfunction "1_1") (pintype "passive"))
      (node (ref "MOTOR") (pin "1") (pinfunction "P1_1") (pintype "passive"))
      (node (ref "U1") (pin "4") (pinfunction "OUT_4") (pintype "passive"))
      (node (ref "U1") (pin "8") (pinfunction "OUT_8") (pintype "passive"))
    )
    (net (code "51") (name "Net-(MOTOR-P2)") (class "Default")
      (node (ref "C11") (pin "2") (pinfunction "2_2") (pintype "passive"))
      (node (ref "C8") (pin "1") (pinfunction "1_1") (pintype "passive"))
      (node (ref "MOTOR") (pin "2") (pinfunction "P2_2") (pintype "passive"))
      (node (ref "U2") (pin "4") (pinfunction "OUT_4") (pintype "passive"))
      (node (ref "U2") (pin "8") (pinfunction "OUT_8") (pintype "passive"))
    )
    (net (code "52") (name "Net-(MOTOR-P3)") (class "Default")
      (node (ref "C14") (pin "1") (pinfunction "1_1") (pintype "passive"))
      (node (ref "C15") (pin "2") (pinfunction "2_2") (pintype "passive"))
      (node (ref "MOTOR") (pin "3") (pinfunction "P3_3") (pintype "passive"))
      (node (ref "U3") (pin "4") (pinfunction "OUT_4") (pintype "passive"))
      (node (ref "U3") (pin "8") (pinfunction "OUT_8") (pintype "passive"))
    )
    (net (code "53") (name "Net-(R19-Pad1)") (class "Default")
      (node (ref "R19") (pin "1") (pinfunction "1_1") (pintype "passive"))
      (node (ref "S1") (pin "1") (pinfunction "1_1") (pintype "passive"))
    )
    (net (code "54") (name "Net-(S2A-1)") (class "Default")
      (node (ref "S2") (pin "P1.1") (pinfunction "1_P1.1") (pintype "passive"))
      (node (ref "U9") (pin "33") (pinfunction "PE2(~{HWB})_33") (pintype "bidirectional"))
    )
    (net (code "55") (name "Net-(S2A-2)") (class "Default")
      (node (ref "R16") (pin "1") (pinfunction "1_1") (pintype "passive"))
      (node (ref "S2") (pin "P1.2") (pinfunction "2_P1.2") (pintype "passive"))
    )
    (net (code "56") (name "Net-(S2B-2)") (class "Default")
      (node (ref "R29") (pin "1") (pinfunction "1_1") (pintype "passive"))
      (node (ref "S2") (pin "P2.2") (pinfunction "2_P2.2") (pintype "passive"))
      (node (ref "U5") (pin "10") (pinfunction "OE_10") (pintype "input"))
      (node (ref "U5") (pin "13") (pinfunction "OE_13") (pintype "input"))
      (node (ref "U5") (pin "4") (pinfunction "OE_4") (pintype "input"))
    )
    (net (code "57") (name "Net-(U1-IN)") (class "Default")
      (node (ref "R3") (pin "2") (pinfunction "2_2") (pintype "passive"))
      (node (ref "U1") (pin "2") (pinfunction "IN_2") (pintype "input"))
    )
    (net (code "58") (name "Net-(U1-INH)") (class "Default")
      (node (ref "R1") (pin "2") (pinfunction "2_2") (pintype "passive"))
      (node (ref "U1") (pin "3") (pinfunction "INH_3") (pintype "input"))
    )
    (net (code "59") (name "Net-(U1-SR)") (class "Default")
      (node (ref "C1") (pin "1") (pinfunction "1_1") (pintype "passive"))
      (node (ref "R4") (pin "2") (pinfunction "2_2") (pintype "passive"))
      (node (ref "U1") (pin "5") (pinfunction "SR_5") (pintype "passive"))
    )
    (net (code "60") (name "Net-(U2-IN)") (class "Default")
      (node (ref "R7") (pin "2") (pinfunction "2_2") (pintype "passive"))
      (node (ref "U2") (pin "2") (pinfunction "IN_2") (pintype "input"))
    )
    (net (code "61") (name "Net-(U2-INH)") (class "Default")
      (node (ref "R5") (pin "2") (pinfunction "2_2") (pintype "passive"))
      (node (ref "U2") (pin "3") (pinfunction "INH_3") (pintype "input"))
    )
    (net (code "62") (name "Net-(U2-SR)") (class "Default")
      (node (ref "C6") (pin "1") (pinfunction "1_1") (pintype "passive"))
      (node (ref "R8") (pin "2") (pinfunction "2_2") (pintype "passive"))
      (node (ref "U2") (pin "5") (pinfunction "SR_5") (pintype "passive"))
    )
    (net (code "63") (name "Net-(U3-IN)") (class "Default")
      (node (ref "R11") (pin "2") (pinfunction "2_2") (pintype "passive"))
      (node (ref "U3") (pin "2") (pinfunction "IN_2") (pintype "input"))
    )
    (net (code "64") (name "Net-(U3-INH)") (class "Default")
      (node (ref "R9") (pin "2") (pinfunction "2_2") (pintype "passive"))
      (node (ref "U3") (pin "3") (pinfunction "INH_3") (pintype "input"))
    )
    (net (code "65") (name "Net-(U3-SR)") (class "Default")
      (node (ref "C10") (pin "1") (pinfunction "1_1") (pintype "passive"))
      (node (ref "R12") (pin "2") (pinfunction "2_2") (pintype "passive"))
      (node (ref "U3") (pin "5") (pinfunction "SR_5") (pintype "passive"))
    )
    (net (code "66") (name "Net-(U5A-O)") (class "Default")
      (node (ref "R22") (pin "1") (pinfunction "1_1") (pintype "passive"))
      (node (ref "U5") (pin "3") (pinfunction "O_3") (pintype "tri_state"))
    )
    (net (code "67") (name "Net-(U5B-O)") (class "Default")
      (node (ref "R23") (pin "1") (pinfunction "1_1") (pintype "passive"))
      (node (ref "U5") (pin "6") (pinfunction "O_6") (pintype "tri_state"))
    )
    (net (code "68") (name "Net-(U5C-O)") (class "Default")
      (node (ref "R24") (pin "1") (pinfunction "1_1") (pintype "passive"))
      (node (ref "U5") (pin "8") (pinfunction "O_8") (pintype "tri_state"))
    )
    (net (code "69") (name "Net-(U5D-O)") (class "Default")
      (node (ref "R25") (pin "1") (pinfunction "1_1") (pintype "passive"))
      (node (ref "U5") (pin "11") (pinfunction "O_11") (pintype "tri_state"))
    )
    (net (code "70") (name "Net-(U6A-B)") (class "Default")
      (node (ref "R37") (pin "2") (pinfunction "2_2") (pintype "passive"))
      (node (ref "U6") (pin "2") (pinfunction "B_2") (pintype "passive"))
      (node (ref "U6") (pin "5") (pinfunction "B_5") (pintype "passive"))
      (node (ref "U6") (pin "6") (pinfunction "C_6") (pintype "passive"))
    )
    (net (code "71") (name "Net-(U7-ADJ)") (class "Default")
      (node (ref "R36") (pin "2") (pinfunction "2_2") (pintype "passive"))
      (node (ref "U7") (pin "5") (pinfunction "ADJ_5") (pintype "passive"))
    )
    (net (code "72") (name "Net-(U8-G)") (class "Default")
      (node (ref "D1") (pin "A") (pinfunction "A_A") (pintype "passive"))
      (node (ref "R14") (pin "2") (pinfunction "2_2") (pintype "passive"))
      (node (ref "U8") (pin "1") (pinfunction "G_1") (pintype "passive"))
    )
    (net (code "73") (name "Net-(U9-AREF)") (class "Default")
      (node (ref "C20") (pin "1") (pinfunction "1_1") (pintype "passive"))
      (node (ref "U9") (pin "42") (pinfunction "AREF_42") (pintype "bidirectional"))
    )
    (net (code "74") (name "Net-(U9-UCAP)") (class "Default")
      (node (ref "C21") (pin "1") (pinfunction "1_1") (pintype "passive"))
      (node (ref "U9") (pin "6") (pinfunction "UCAP_6") (pintype "bidirectional"))
    )
    (net (code "75") (name "Net-(U9-XTAL1)") (class "Default")
      (node (ref "C19") (pin "1") (pinfunction "1_1") (pintype "passive"))
      (node (ref "R13") (pin "1") (pinfunction "1_1") (pintype "passive"))
      (node (ref "U9") (pin "17") (pinfunction "XTAL1_17") (pintype "bidirectional"))
      (node (ref "XTAL1") (pin "2") (pinfunction "2_2") (pintype "passive"))
    )
    (net (code "76") (name "Net-(U9-XTAL2)") (class "Default")
      (node (ref "C18") (pin "1") (pinfunction "1_1") (pintype "passive"))
      (node (ref "R13") (pin "2") (pinfunction "2_2") (pintype "passive"))
      (node (ref "U9") (pin "16") (pinfunction "XTAL2_16") (pintype "bidirectional"))
      (node (ref "XTAL1") (pin "1") (pinfunction "1_1") (pintype "passive"))
    )
    (net (code "77") (name "Net-(U10B-O)") (class "Default")
      (node (ref "R28") (pin "2") (pinfunction "2_2") (pintype "passive"))
      (node (ref "U10") (pin "6") (pinfunction "O_6") (pintype "tri_state"))
    )
    (net (code "78") (name "Net-(U11-G)") (class "Default")
      (node (ref "R38") (pin "2") (pinfunction "2_2") (pintype "passive"))
      (node (ref "U11") (pin "1") (pinfunction "G_1") (pintype "passive"))
      (node (ref "U6") (pin "3") (pinfunction "C_3") (pintype "passive"))
    )
    (net (code "79") (name "Net-(U12A-D)") (class "Default")
      (node (ref "LED") (pin "B") (pinfunction "B_B") (pintype "passive"))
      (node (ref "U12") (pin "6") (pinfunction "D_6") (pintype "passive"))
    )
    (net (code "80") (name "Net-(U12B-D)") (class "Default")
      (node (ref "LED") (pin "G") (pinfunction "G_G") (pintype "passive"))
      (node (ref "U12") (pin "3") (pinfunction "D_3") (pintype "passive"))
    )
    (net (code "81") (name "Net-(USB-D+)") (class "Default")
      (node (ref "R17") (pin "1") (pinfunction "1_1") (pintype "passive"))
      (node (ref "USB") (pin "3") (pinfunction "D+_3") (pintype "bidirectional"))
    )
    (net (code "82") (name "Net-(USB-D-)") (class "Default")
      (node (ref "R18") (pin "1") (pinfunction "1_1") (pintype "passive"))
      (node (ref "USB") (pin "2") (pinfunction "D-_2") (pintype "bidirectional"))
    )
    (net (code "83") (name "VPP") (class "Default")
      (node (ref "C11") (pin "1") (pinfunction "1_1") (pintype "passive"))
      (node (ref "C12") (pin "1") (pinfunction "1_1") (pintype "passive"))
      (node (ref "C13") (pin "1") (pinfunction "1_1") (pintype "passive"))
      (node (ref "C15") (pin "1") (pinfunction "1_1") (pintype "passive"))
      (node (ref "C16") (pin "+") (pinfunction "+_+") (pintype "passive"))
      (node (ref "C3") (pin "1") (pinfunction "1_1") (pintype "passive"))
      (node (ref "C40") (pin "1") (pinfunction "1_1") (pintype "passive"))
      (node (ref "C7") (pin "1") (pinfunction "1_1") (pintype "passive"))
      (node (ref "D1") (pin "C") (pinfunction "C_C") (pintype "passive"))
      (node (ref "D2") (pin "C") (pinfunction "C_C") (pintype "passive"))
      (node (ref "U1") (pin "7") (pinfunction "VS_7") (pintype "passive"))
      (node (ref "U2") (pin "7") (pinfunction "VS_7") (pintype "passive"))
      (node (ref "U3") (pin "7") (pinfunction "VS_7") (pintype "passive"))
      (node (ref "U8") (pin "3") (pinfunction "S_3") (pintype "passive"))
    )
    (net (code "84") (name "unconnected-(J1-GPIO4-Pad7)") (class "Default")
      (node (ref "J1") (pin "7") (pinfunction "GPIO4_7") (pintype "passive"))
    )
    (net (code "85") (name "unconnected-(J1-GPIO5-Pad29)") (class "Default")
      (node (ref "J1") (pin "29") (pinfunction "GPIO5_29") (pintype "passive"))
    )
    (net (code "86") (name "unconnected-(J1-GPIO6-Pad31)") (class "Default")
      (node (ref "J1") (pin "31") (pinfunction "GPIO6_31") (pintype "passive"))
    )
    (net (code "87") (name "unconnected-(J1-GPIO7{slash}CE1-Pad26)") (class "Default")
      (node (ref "J1") (pin "26") (pinfunction "GPIO7/CE1_26") (pintype "passive"))
    )
    (net (code "88") (name "unconnected-(J1-GPIO12-Pad32)") (class "Default")
      (node (ref "J1") (pin "32") (pinfunction "GPIO12_32") (pintype "passive"))
    )
    (net (code "89") (name "unconnected-(J1-GPIO13-Pad33)") (class "Default")
      (node (ref "J1") (pin "33") (pinfunction "GPIO13_33") (pintype "passive"))
    )
    (net (code "90") (name "unconnected-(J1-GPIO16-Pad36)") (class "Default")
      (node (ref "J1") (pin "36") (pinfunction "GPIO16_36") (pintype "passive"))
    )
    (net (code "91") (name "unconnected-(J1-GPIO17-Pad11)") (class "Default")
      (node (ref "J1") (pin "11") (pinfunction "GPIO17_11") (pintype "passive"))
    )
    (net (code "92") (name "unconnected-(J1-GPIO19-Pad35)") (class "Default")
      (node (ref "J1") (pin "35") (pinfunction "GPIO19_35") (pintype "passive"))
    )
    (net (code "93") (name "unconnected-(J1-GPIO20-Pad38)") (class "Default")
      (node (ref "J1") (pin "38") (pinfunction "GPIO20_38") (pintype "passive"))
    )
    (net (code "94") (name "unconnected-(J1-GPIO21-Pad40)") (class "Default")
      (node (ref "J1") (pin "40") (pinfunction "GPIO21_40") (pintype "passive"))
    )
    (net (code "95") (name "unconnected-(J1-GPIO22-Pad15)") (class "Default")
      (node (ref "J1") (pin "15") (pinfunction "GPIO22_15") (pintype "passive"))
    )
    (net (code "96") (name "unconnected-(J1-GPIO24-Pad18)") (class "Default")
      (node (ref "J1") (pin "18") (pinfunction "GPIO24_18") (pintype "passive"))
    )
    (net (code "97") (name "unconnected-(J1-GPIO26-Pad37)") (class "Default")
      (node (ref "J1") (pin "37") (pinfunction "GPIO26_37") (pintype "passive"))
    )
    (net (code "98") (name "unconnected-(J1-GPIO27-Pad13)") (class "Default")
      (node (ref "J1") (pin "13") (pinfunction "GPIO27_13") (pintype "passive"))
    )
    (net (code "99") (name "unconnected-(U7-INH-Pad1)") (class "Default")
      (node (ref "U7") (pin "1") (pinfunction "INH_1") (pintype "open_collector"))
    )
    (net (code "100") (name "unconnected-(U10D-O-Pad11)") (class "Default")
      (node (ref "U10") (pin "11") (pinfunction "O_11") (pintype "tri_state"))
    )
    (net (code "101") (name "unconnected-(USB-ID-Pad4)") (class "Default")
      (node (ref "USB") (pin "4") (pinfunction "ID_4") (pintype "bidirectional"))
    )
  )
)
